# fpgaTop.net
KiCad netlist of a schematic drawn in Altium Designer
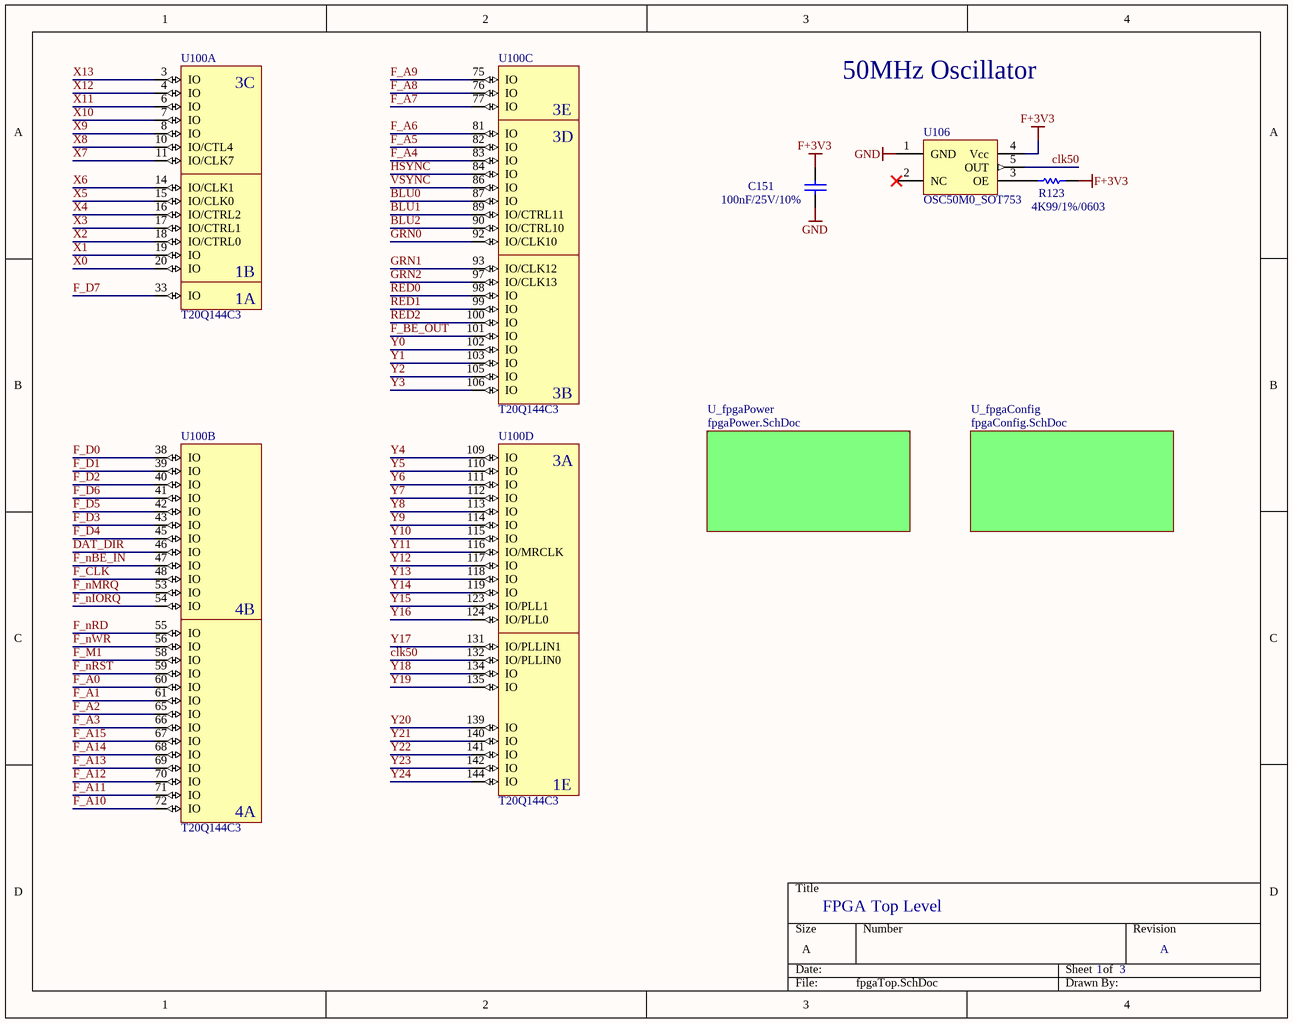
[diagram p0: fpgaTop.SchDoc]

(export (version "E")
  (design (tool "Eeschema 10.0.6"))
  (components
    (comp (ref "C151")
      (value "100nF/25V/10%")
      (footprint "MY0603")
      (description "0.1µF ±10% 25V Ceramic Capacitor X7R 0603 (1608 Metric)")
      (fields (field (name "MFG") "AVX"))
      (libsource (lib "Capacitors") (part "CAP100NF25V"))
    )
    (comp (ref "R123")
      (value "4K99/1%/0603")
      (footprint "0603")
      (description "4.99k Ohm ±1% 0.1W, 1/10W Chip Resistor 0603 (1608 Metric) Moisture Resistant Thick Film")
      (fields (field (name "MFG") "Yageo"))
      (libsource (lib "Resistors") (part "RES4K99"))
    )
    (comp (ref "U100")
      (value "T20Q144C3")
      (footprint "LQFP144")
      (description "Trion® Field Programmable Gate Array (FPGA) IC 97 1044 19728 144-LQFP")
      (fields (field (name "MFG") "Efinix"))
      (libsource (lib "DigitalIC") (part "T20Q144C3"))
    )
    (comp (ref "U106")
      (value "OSC50M0_SOT753")
      (footprint "SOT753")
      (description "50 MHz XO (Standard) HCMOS, LVCMOS Oscillator 2.5V ~ 3.3V Standby (Power Down) SC-74A, SOT-753")
      (fields (field (name "MFG") "SiTime"))
      (libsource (lib "MiscSemi") (part "OSC50M0_SOT753"))
    )
  )
  (nets
    (net (code "1") (name "/BLU0") (class "Default")
      (node (ref "U100") (pin "87") (pinfunction "IO_87") (pintype "bidirectional"))
    )
    (net (code "2") (name "/BLU1") (class "Default")
      (node (ref "U100") (pin "89") (pinfunction "IO/CTRL11_89") (pintype "bidirectional"))
    )
    (net (code "3") (name "/BLU2") (class "Default")
      (node (ref "U100") (pin "90") (pinfunction "IO/CTRL10_90") (pintype "bidirectional"))
    )
    (net (code "4") (name "/DAT_DIR") (class "Default")
      (node (ref "U100") (pin "46") (pinfunction "IO_46") (pintype "bidirectional"))
    )
    (net (code "5") (name "/F_A0") (class "Default")
      (node (ref "U100") (pin "60") (pinfunction "IO_60") (pintype "bidirectional"))
    )
    (net (code "6") (name "/F_A1") (class "Default")
      (node (ref "U100") (pin "61") (pinfunction "IO_61") (pintype "bidirectional"))
    )
    (net (code "7") (name "/F_A2") (class "Default")
      (node (ref "U100") (pin "65") (pinfunction "IO_65") (pintype "bidirectional"))
    )
    (net (code "8") (name "/F_A3") (class "Default")
      (node (ref "U100") (pin "66") (pinfunction "IO_66") (pintype "bidirectional"))
    )
    (net (code "9") (name "/F_A4") (class "Default")
      (node (ref "U100") (pin "83") (pinfunction "IO_83") (pintype "bidirectional"))
    )
    (net (code "10") (name "/F_A5") (class "Default")
      (node (ref "U100") (pin "82") (pinfunction "IO_82") (pintype "bidirectional"))
    )
    (net (code "11") (name "/F_A6") (class "Default")
      (node (ref "U100") (pin "81") (pinfunction "IO_81") (pintype "bidirectional"))
    )
    (net (code "12") (name "/F_A7") (class "Default")
      (node (ref "U100") (pin "77") (pinfunction "IO_77") (pintype "bidirectional"))
    )
    (net (code "13") (name "/F_A8") (class "Default")
      (node (ref "U100") (pin "76") (pinfunction "IO_76") (pintype "bidirectional"))
    )
    (net (code "14") (name "/F_A9") (class "Default")
      (node (ref "U100") (pin "75") (pinfunction "IO_75") (pintype "bidirectional"))
    )
    (net (code "15") (name "/F_A10") (class "Default")
      (node (ref "U100") (pin "72") (pinfunction "IO_72") (pintype "bidirectional"))
    )
    (net (code "16") (name "/F_A11") (class "Default")
      (node (ref "U100") (pin "71") (pinfunction "IO_71") (pintype "bidirectional"))
    )
    (net (code "17") (name "/F_A12") (class "Default")
      (node (ref "U100") (pin "70") (pinfunction "IO_70") (pintype "bidirectional"))
    )
    (net (code "18") (name "/F_A13") (class "Default")
      (node (ref "U100") (pin "69") (pinfunction "IO_69") (pintype "bidirectional"))
    )
    (net (code "19") (name "/F_A14") (class "Default")
      (node (ref "U100") (pin "68") (pinfunction "IO_68") (pintype "bidirectional"))
    )
    (net (code "20") (name "/F_A15") (class "Default")
      (node (ref "U100") (pin "67") (pinfunction "IO_67") (pintype "bidirectional"))
    )
    (net (code "21") (name "/F_BE_OUT") (class "Default")
      (node (ref "U100") (pin "101") (pinfunction "IO_101") (pintype "bidirectional"))
    )
    (net (code "22") (name "/F_CLK") (class "Default")
      (node (ref "U100") (pin "48") (pinfunction "IO_48") (pintype "bidirectional"))
    )
    (net (code "23") (name "/F_D0") (class "Default")
      (node (ref "U100") (pin "38") (pinfunction "IO_38") (pintype "bidirectional"))
    )
    (net (code "24") (name "/F_D1") (class "Default")
      (node (ref "U100") (pin "39") (pinfunction "IO_39") (pintype "bidirectional"))
    )
    (net (code "25") (name "/F_D2") (class "Default")
      (node (ref "U100") (pin "40") (pinfunction "IO_40") (pintype "bidirectional"))
    )
    (net (code "26") (name "/F_D3") (class "Default")
      (node (ref "U100") (pin "43") (pinfunction "IO_43") (pintype "bidirectional"))
    )
    (net (code "27") (name "/F_D4") (class "Default")
      (node (ref "U100") (pin "45") (pinfunction "IO_45") (pintype "bidirectional"))
    )
    (net (code "28") (name "/F_D5") (class "Default")
      (node (ref "U100") (pin "42") (pinfunction "IO_42") (pintype "bidirectional"))
    )
    (net (code "29") (name "/F_D6") (class "Default")
      (node (ref "U100") (pin "41") (pinfunction "IO_41") (pintype "bidirectional"))
    )
    (net (code "30") (name "/F_D7") (class "Default")
      (node (ref "U100") (pin "33") (pinfunction "IO_33") (pintype "bidirectional"))
    )
    (net (code "31") (name "/F_M1") (class "Default")
      (node (ref "U100") (pin "58") (pinfunction "IO_58") (pintype "bidirectional"))
    )
    (net (code "32") (name "/F_nBE_IN") (class "Default")
      (node (ref "U100") (pin "47") (pinfunction "IO_47") (pintype "bidirectional"))
    )
    (net (code "33") (name "/F_nIORQ") (class "Default")
      (node (ref "U100") (pin "54") (pinfunction "IO_54") (pintype "bidirectional"))
    )
    (net (code "34") (name "/F_nMRQ") (class "Default")
      (node (ref "U100") (pin "53") (pinfunction "IO_53") (pintype "bidirectional"))
    )
    (net (code "35") (name "/F_nRD") (class "Default")
      (node (ref "U100") (pin "55") (pinfunction "IO_55") (pintype "bidirectional"))
    )
    (net (code "36") (name "/F_nRST") (class "Default")
      (node (ref "U100") (pin "59") (pinfunction "IO_59") (pintype "bidirectional"))
    )
    (net (code "37") (name "/F_nWR") (class "Default")
      (node (ref "U100") (pin "56") (pinfunction "IO_56") (pintype "bidirectional"))
    )
    (net (code "38") (name "/GRN0") (class "Default")
      (node (ref "U100") (pin "92") (pinfunction "IO/CLK10_92") (pintype "bidirectional"))
    )
    (net (code "39") (name "/GRN1") (class "Default")
      (node (ref "U100") (pin "93") (pinfunction "IO/CLK12_93") (pintype "bidirectional"))
    )
    (net (code "40") (name "/GRN2") (class "Default")
      (node (ref "U100") (pin "97") (pinfunction "IO/CLK13_97") (pintype "bidirectional"))
    )
    (net (code "41") (name "/HSYNC") (class "Default")
      (node (ref "U100") (pin "84") (pinfunction "IO_84") (pintype "bidirectional"))
    )
    (net (code "42") (name "/RED0") (class "Default")
      (node (ref "U100") (pin "98") (pinfunction "IO_98") (pintype "bidirectional"))
    )
    (net (code "43") (name "/RED1") (class "Default")
      (node (ref "U100") (pin "99") (pinfunction "IO_99") (pintype "bidirectional"))
    )
    (net (code "44") (name "/RED2") (class "Default")
      (node (ref "U100") (pin "100") (pinfunction "IO_100") (pintype "bidirectional"))
    )
    (net (code "45") (name "/VSYNC") (class "Default")
      (node (ref "U100") (pin "86") (pinfunction "IO_86") (pintype "bidirectional"))
    )
    (net (code "46") (name "/X0") (class "Default")
      (node (ref "U100") (pin "20") (pinfunction "IO_20") (pintype "bidirectional"))
    )
    (net (code "47") (name "/X1") (class "Default")
      (node (ref "U100") (pin "19") (pinfunction "IO_19") (pintype "bidirectional"))
    )
    (net (code "48") (name "/X2") (class "Default")
      (node (ref "U100") (pin "18") (pinfunction "IO/CTRL0_18") (pintype "bidirectional"))
    )
    (net (code "49") (name "/X3") (class "Default")
      (node (ref "U100") (pin "17") (pinfunction "IO/CTRL1_17") (pintype "bidirectional"))
    )
    (net (code "50") (name "/X4") (class "Default")
      (node (ref "U100") (pin "16") (pinfunction "IO/CTRL2_16") (pintype "bidirectional"))
    )
    (net (code "51") (name "/X5") (class "Default")
      (node (ref "U100") (pin "15") (pinfunction "IO/CLK0_15") (pintype "bidirectional"))
    )
    (net (code "52") (name "/X6") (class "Default")
      (node (ref "U100") (pin "14") (pinfunction "IO/CLK1_14") (pintype "bidirectional"))
    )
    (net (code "53") (name "/X7") (class "Default")
      (node (ref "U100") (pin "11") (pinfunction "IO/CLK7_11") (pintype "bidirectional"))
    )
    (net (code "54") (name "/X8") (class "Default")
      (node (ref "U100") (pin "10") (pinfunction "IO/CTL4_10") (pintype "bidirectional"))
    )
    (net (code "55") (name "/X9") (class "Default")
      (node (ref "U100") (pin "8") (pinfunction "IO_8") (pintype "bidirectional"))
    )
    (net (code "56") (name "/X10") (class "Default")
      (node (ref "U100") (pin "7") (pinfunction "IO_7") (pintype "bidirectional"))
    )
    (net (code "57") (name "/X11") (class "Default")
      (node (ref "U100") (pin "6") (pinfunction "IO_6") (pintype "bidirectional"))
    )
    (net (code "58") (name "/X12") (class "Default")
      (node (ref "U100") (pin "4") (pinfunction "IO_4") (pintype "bidirectional"))
    )
    (net (code "59") (name "/X13") (class "Default")
      (node (ref "U100") (pin "3") (pinfunction "IO_3") (pintype "bidirectional"))
    )
    (net (code "60") (name "/Y0") (class "Default")
      (node (ref "U100") (pin "102") (pinfunction "IO_102") (pintype "bidirectional"))
    )
    (net (code "61") (name "/Y1") (class "Default")
      (node (ref "U100") (pin "103") (pinfunction "IO_103") (pintype "bidirectional"))
    )
    (net (code "62") (name "/Y2") (class "Default")
      (node (ref "U100") (pin "105") (pinfunction "IO_105") (pintype "bidirectional"))
    )
    (net (code "63") (name "/Y3") (class "Default")
      (node (ref "U100") (pin "106") (pinfunction "IO_106") (pintype "bidirectional"))
    )
    (net (code "64") (name "/Y4") (class "Default")
      (node (ref "U100") (pin "109") (pinfunction "IO_109") (pintype "bidirectional"))
    )
    (net (code "65") (name "/Y5") (class "Default")
      (node (ref "U100") (pin "110") (pinfunction "IO_110") (pintype "bidirectional"))
    )
    (net (code "66") (name "/Y6") (class "Default")
      (node (ref "U100") (pin "111") (pinfunction "IO_111") (pintype "bidirectional"))
    )
    (net (code "67") (name "/Y7") (class "Default")
      (node (ref "U100") (pin "112") (pinfunction "IO_112") (pintype "bidirectional"))
    )
    (net (code "68") (name "/Y8") (class "Default")
      (node (ref "U100") (pin "113") (pinfunction "IO_113") (pintype "bidirectional"))
    )
    (net (code "69") (name "/Y9") (class "Default")
      (node (ref "U100") (pin "114") (pinfunction "IO_114") (pintype "bidirectional"))
    )
    (net (code "70") (name "/Y10") (class "Default")
      (node (ref "U100") (pin "115") (pinfunction "IO_115") (pintype "bidirectional"))
    )
    (net (code "71") (name "/Y11") (class "Default")
      (node (ref "U100") (pin "116") (pinfunction "IO/MRCLK_116") (pintype "bidirectional"))
    )
    (net (code "72") (name "/Y12") (class "Default")
      (node (ref "U100") (pin "117") (pinfunction "IO_117") (pintype "bidirectional"))
    )
    (net (code "73") (name "/Y13") (class "Default")
      (node (ref "U100") (pin "118") (pinfunction "IO_118") (pintype "bidirectional"))
    )
    (net (code "74") (name "/Y14") (class "Default")
      (node (ref "U100") (pin "119") (pinfunction "IO_119") (pintype "bidirectional"))
    )
    (net (code "75") (name "/Y15") (class "Default")
      (node (ref "U100") (pin "123") (pinfunction "IO/PLL1_123") (pintype "bidirectional"))
    )
    (net (code "76") (name "/Y16") (class "Default")
      (node (ref "U100") (pin "124") (pinfunction "IO/PLL0_124") (pintype "bidirectional"))
    )
    (net (code "77") (name "/Y17") (class "Default")
      (node (ref "U100") (pin "131") (pinfunction "IO/PLLIN1_131") (pintype "bidirectional"))
    )
    (net (code "78") (name "/Y18") (class "Default")
      (node (ref "U100") (pin "134") (pinfunction "IO_134") (pintype "bidirectional"))
    )
    (net (code "79") (name "/Y19") (class "Default")
      (node (ref "U100") (pin "135") (pinfunction "IO_135") (pintype "bidirectional"))
    )
    (net (code "80") (name "/Y20") (class "Default")
      (node (ref "U100") (pin "139") (pinfunction "IO_139") (pintype "bidirectional"))
    )
    (net (code "81") (name "/Y21") (class "Default")
      (node (ref "U100") (pin "140") (pinfunction "IO_140") (pintype "bidirectional"))
    )
    (net (code "82") (name "/Y22") (class "Default")
      (node (ref "U100") (pin "141") (pinfunction "IO_141") (pintype "bidirectional"))
    )
    (net (code "83") (name "/Y23") (class "Default")
      (node (ref "U100") (pin "142") (pinfunction "IO_142") (pintype "bidirectional"))
    )
    (net (code "84") (name "/Y24") (class "Default")
      (node (ref "U100") (pin "144") (pinfunction "IO_144") (pintype "bidirectional"))
    )
    (net (code "85") (name "/clk50") (class "Default")
      (node (ref "U100") (pin "132") (pinfunction "IO/PLLIN0_132") (pintype "bidirectional"))
      (node (ref "U106") (pin "5") (pinfunction "OUT_5") (pintype "output"))
    )
    (net (code "86") (name "F+3V3") (class "Default")
      (node (ref "C151") (pin "2") (pinfunction "2_2") (pintype "passive"))
      (node (ref "R123") (pin "1") (pinfunction "1_1") (pintype "passive"))
      (node (ref "U106") (pin "4") (pinfunction "Vcc_4") (pintype "power_in"))
    )
    (net (code "87") (name "GND") (class "Default")
      (node (ref "C151") (pin "1") (pinfunction "1_1") (pintype "passive"))
      (node (ref "U106") (pin "1") (pinfunction "GND_1") (pintype "power_in"))
    )
    (net (code "88") (name "Net-(U106-OE)") (class "Default")
      (node (ref "R123") (pin "2") (pinfunction "2_2") (pintype "passive"))
      (node (ref "U106") (pin "3") (pinfunction "OE_3") (pintype "passive"))
    )
    (net (code "89") (name "unconnected-(U106-NC-Pad2)") (class "Default")
      (node (ref "U106") (pin "2") (pinfunction "NC_2") (pintype "power_in+no_connect"))
    )
  )
)
